# Steering_Controller.net
KiCad netlist of a schematic drawn in EAGLE
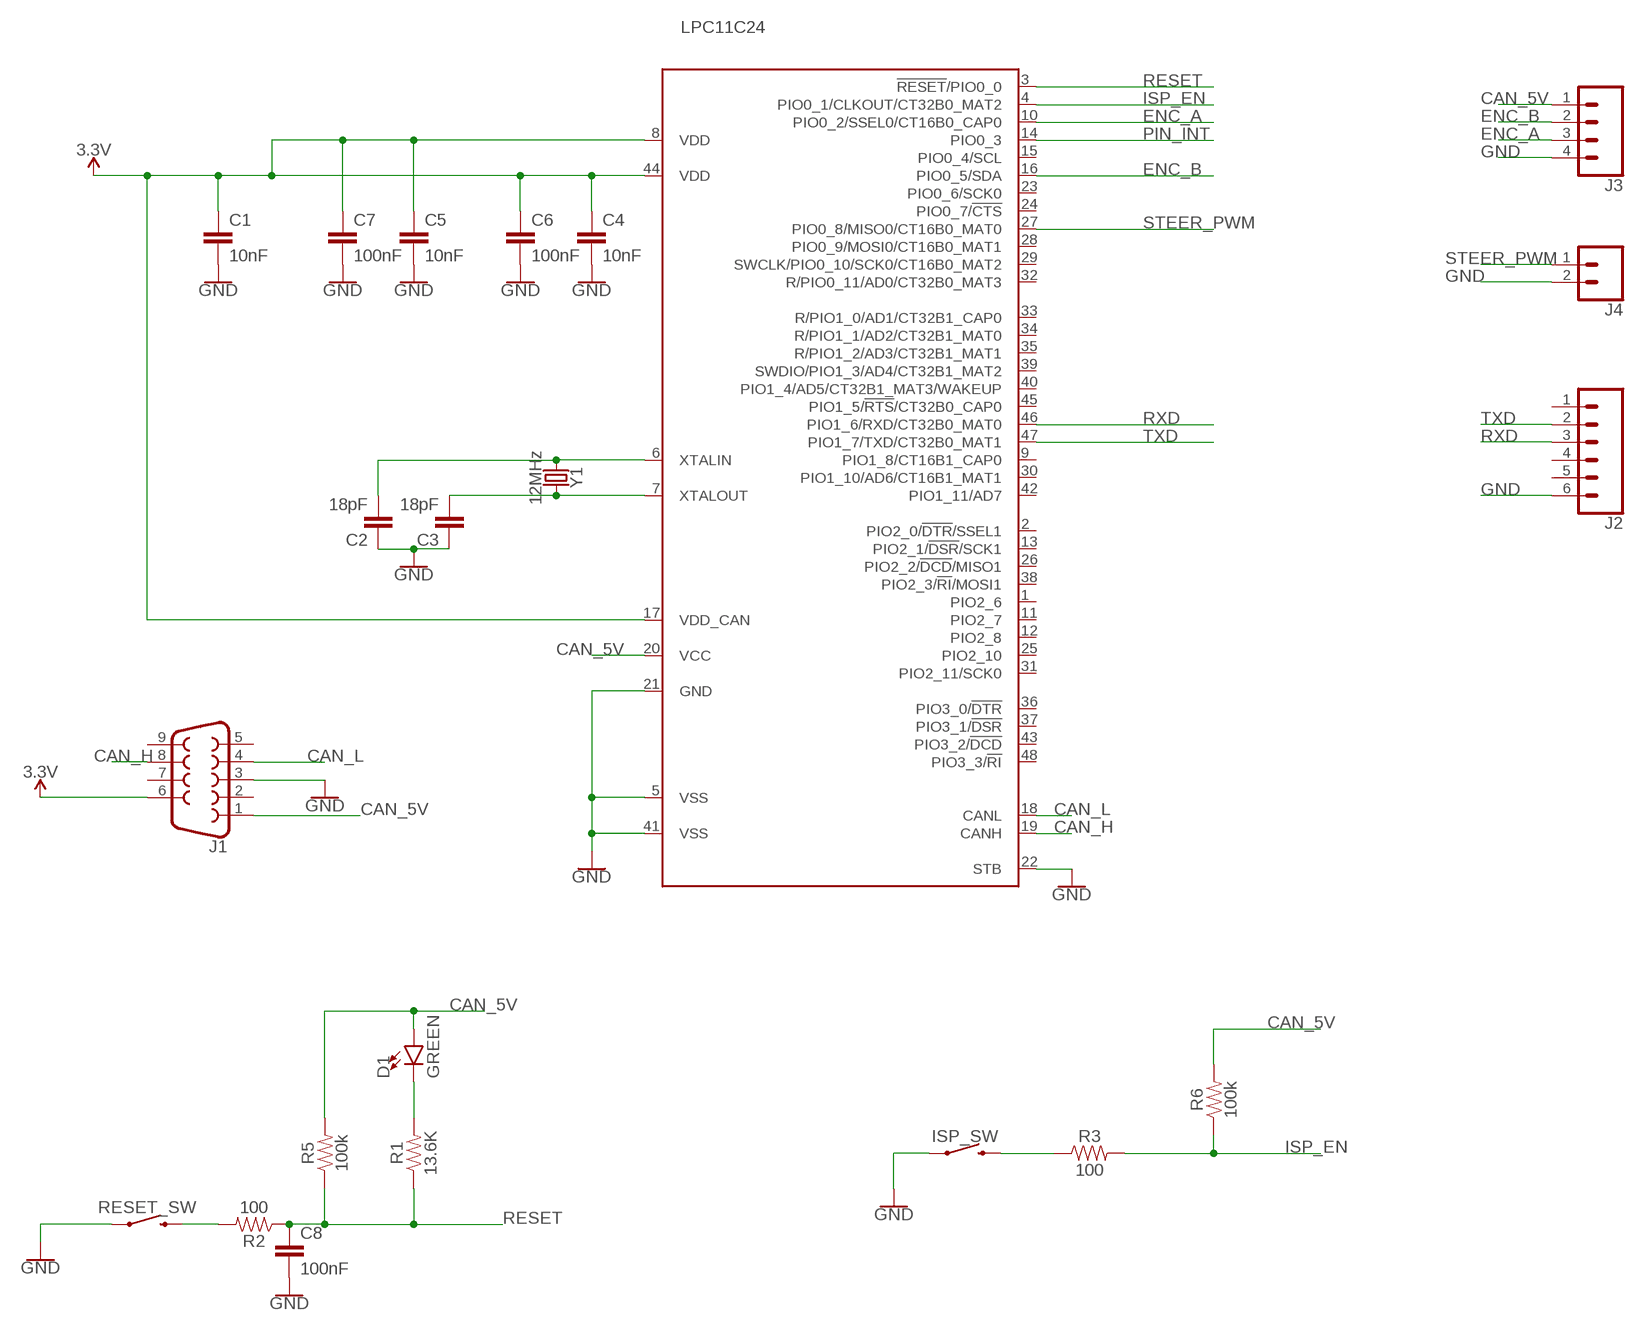
[diagram p0: schematic, sheet 1]

(export (version "E")
  (design (tool "Eeschema 10.0.6"))
  (components
    (comp (ref "C1")
      (value "10nF")
      (footprint "eagle-import:CAP-PTH-2.54")
      (libsource (lib "eagle-import") (part "22PF-PTH-2.54MM-200V-5%"))
    )
    (comp (ref "C2")
      (value "18pF")
      (footprint "eagle-import:CAP-PTH-2.54")
      (libsource (lib "eagle-import") (part "22PF-PTH-2.54MM-200V-5%"))
    )
    (comp (ref "C3")
      (value "18pF")
      (footprint "eagle-import:CAP-PTH-2.54")
      (libsource (lib "eagle-import") (part "22PF-PTH-2.54MM-200V-5%"))
    )
    (comp (ref "C4")
      (value "10nF")
      (footprint "eagle-import:CAP-PTH-2.54")
      (libsource (lib "eagle-import") (part "22PF-PTH-2.54MM-200V-5%"))
    )
    (comp (ref "C5")
      (value "10nF")
      (footprint "eagle-import:CAP-PTH-2.54")
      (libsource (lib "eagle-import") (part "22PF-PTH-2.54MM-200V-5%"))
    )
    (comp (ref "C6")
      (value "100nF")
      (footprint "eagle-import:CAP-PTH-2.54")
      (libsource (lib "eagle-import") (part "22PF-PTH-2.54MM-200V-5%"))
    )
    (comp (ref "C7")
      (value "100nF")
      (footprint "eagle-import:CAP-PTH-2.54")
      (libsource (lib "eagle-import") (part "22PF-PTH-2.54MM-200V-5%"))
    )
    (comp (ref "C8")
      (value "100nF")
      (footprint "eagle-import:CAP-PTH-2.54")
      (libsource (lib "eagle-import") (part "22PF-PTH-2.54MM-200V-5%"))
    )
    (comp (ref "D1")
      (value "GREEN")
      (footprint "eagle-import:LED-1206")
      (libsource (lib "eagle-import") (part "LED-GREEN1206"))
    )
    (comp (ref "ISP_SW")
      (value "MOMENTARY-SWITCH-SPST-PTH-6.0MM")
      (footprint "eagle-import:TACTILE_SWITCH_PTH_6.0MM")
      (libsource (lib "eagle-import") (part "MOMENTARY-SWITCH-SPST-PTH-6.0MM"))
    )
    (comp (ref "J1")
      (value "DB9FEMALE")
      (footprint "eagle-import:DB9")
      (libsource (lib "eagle-import") (part "DB9FEMALE"))
    )
    (comp (ref "J2")
      (value "CONN_06SILK_FEMALE_PTH")
      (footprint "eagle-import:1X06")
      (libsource (lib "eagle-import") (part "CONN_06SILK_FEMALE_PTH"))
    )
    (comp (ref "J3")
      (value "CONN_04")
      (footprint "eagle-import:1X04")
      (libsource (lib "eagle-import") (part "CONN_04"))
    )
    (comp (ref "J4")
      (value "CONN_02")
      (footprint "eagle-import:1X02")
      (libsource (lib "eagle-import") (part "CONN_02"))
    )
    (comp (ref "LPC11C24")
      (value "LPC11C22/24-LQFP48")
      (footprint "eagle-import:LQFP48")
      (libsource (lib "eagle-import") (part "LPC11C22/24-LQFP48"))
    )
    (comp (ref "R1")
      (value "13.6K")
      (footprint "eagle-import:AXIAL-0.3")
      (libsource (lib "eagle-import") (part "100KOHM-HORIZ-1/4W-1%"))
    )
    (comp (ref "R2")
      (value "100")
      (footprint "eagle-import:AXIAL-0.3")
      (libsource (lib "eagle-import") (part "100KOHM-HORIZ-1/4W-1%"))
    )
    (comp (ref "R3")
      (value "100")
      (footprint "eagle-import:AXIAL-0.3")
      (libsource (lib "eagle-import") (part "100OHM-HORIZ-1/4W-1%"))
    )
    (comp (ref "R5")
      (value "100k")
      (footprint "eagle-import:AXIAL-0.3")
      (libsource (lib "eagle-import") (part "100KOHM-HORIZ-1/4W-1%"))
    )
    (comp (ref "R6")
      (value "100k")
      (footprint "eagle-import:AXIAL-0.3")
      (libsource (lib "eagle-import") (part "100KOHM-HORIZ-1/4W-1%"))
    )
    (comp (ref "RESET_SW")
      (value "MOMENTARY-SWITCH-SPST-PTH-6.0MM")
      (footprint "eagle-import:TACTILE_SWITCH_PTH_6.0MM")
      (libsource (lib "eagle-import") (part "MOMENTARY-SWITCH-SPST-PTH-6.0MM"))
    )
    (comp (ref "Y1")
      (value "12MHz")
      (footprint "eagle-import:HC49US")
      (libsource (lib "eagle-import") (part "CRYSTAL-16MHZPTH-HC49US"))
    )
  )
  (nets
    (net (code "1") (name "/CAN_5V") (class "Default")
      (node (ref "D1") (pin "A") (pinfunction "A_A") (pintype "passive"))
      (node (ref "J1") (pin "1") (pinfunction "1_1") (pintype "passive"))
      (node (ref "J3") (pin "1") (pinfunction "1_1") (pintype "passive"))
      (node (ref "LPC11C24") (pin "20") (pinfunction "VCC_20") (pintype "power_in"))
      (node (ref "R5") (pin "P$2") (pinfunction "2_P$2") (pintype "passive"))
      (node (ref "R6") (pin "P$2") (pinfunction "2_P$2") (pintype "passive"))
    )
    (net (code "2") (name "/CAN_H") (class "Default")
      (node (ref "J1") (pin "8") (pinfunction "8_8") (pintype "passive"))
      (node (ref "LPC11C24") (pin "19") (pinfunction "CANH_19") (pintype "bidirectional"))
    )
    (net (code "3") (name "/CAN_L") (class "Default")
      (node (ref "J1") (pin "4") (pinfunction "4_4") (pintype "passive"))
      (node (ref "LPC11C24") (pin "18") (pinfunction "CANL_18") (pintype "bidirectional"))
    )
    (net (code "4") (name "/ENC_A") (class "Default")
      (node (ref "J3") (pin "3") (pinfunction "3_3") (pintype "passive"))
      (node (ref "LPC11C24") (pin "10") (pinfunction "PIO0_2/SSEL0/CT16B0_CAP0_10") (pintype "bidirectional"))
    )
    (net (code "5") (name "/ENC_B") (class "Default")
      (node (ref "J3") (pin "2") (pinfunction "2_2") (pintype "passive"))
      (node (ref "LPC11C24") (pin "16") (pinfunction "PIO0_5/SDA_16") (pintype "bidirectional"))
    )
    (net (code "6") (name "/ISP_EN") (class "Default")
      (node (ref "LPC11C24") (pin "4") (pinfunction "PIO0_1/CLKOUT/CT32B0_MAT2_4") (pintype "bidirectional"))
      (node (ref "R3") (pin "P$2") (pinfunction "2_P$2") (pintype "passive"))
      (node (ref "R6") (pin "P$1") (pinfunction "1_P$1") (pintype "passive"))
    )
    (net (code "7") (name "/PIN_INT") (class "Default")
      (node (ref "LPC11C24") (pin "14") (pinfunction "PIO0_3_14") (pintype "bidirectional"))
    )
    (net (code "8") (name "/RESET") (class "Default")
      (node (ref "C8") (pin "1") (pinfunction "1_1") (pintype "passive"))
      (node (ref "LPC11C24") (pin "3") (pinfunction "~{RESET}/PIO0_0_3") (pintype "bidirectional"))
      (node (ref "R1") (pin "P$1") (pinfunction "1_P$1") (pintype "passive"))
      (node (ref "R2") (pin "P$1") (pinfunction "1_P$1") (pintype "passive"))
      (node (ref "R5") (pin "P$1") (pinfunction "1_P$1") (pintype "passive"))
    )
    (net (code "9") (name "/RXD") (class "Default")
      (node (ref "J2") (pin "3") (pinfunction "3_3") (pintype "passive"))
      (node (ref "LPC11C24") (pin "46") (pinfunction "PIO1_6/RXD/CT32B0_MAT0_46") (pintype "bidirectional"))
    )
    (net (code "10") (name "/STEER_PWM") (class "Default")
      (node (ref "J4") (pin "1") (pinfunction "1_1") (pintype "passive"))
      (node (ref "LPC11C24") (pin "27") (pinfunction "PIO0_8/MISO0/CT16B0_MAT0_27") (pintype "bidirectional"))
    )
    (net (code "11") (name "/TXD") (class "Default")
      (node (ref "J2") (pin "2") (pinfunction "2_2") (pintype "passive"))
      (node (ref "LPC11C24") (pin "47") (pinfunction "PIO1_7/TXD/CT32B0_MAT1_47") (pintype "bidirectional"))
    )
    (net (code "12") (name "3.3V") (class "Default")
      (node (ref "C1") (pin "1") (pinfunction "1_1") (pintype "passive"))
      (node (ref "C4") (pin "1") (pinfunction "1_1") (pintype "passive"))
      (node (ref "C5") (pin "1") (pinfunction "1_1") (pintype "passive"))
      (node (ref "C6") (pin "1") (pinfunction "1_1") (pintype "passive"))
      (node (ref "C7") (pin "1") (pinfunction "1_1") (pintype "passive"))
      (node (ref "J1") (pin "6") (pinfunction "6_6") (pintype "passive"))
      (node (ref "LPC11C24") (pin "17") (pinfunction "VDD_CAN_17") (pintype "power_in"))
      (node (ref "LPC11C24") (pin "44") (pinfunction "VDD_44") (pintype "power_in"))
      (node (ref "LPC11C24") (pin "8") (pinfunction "VDD_8") (pintype "power_in"))
    )
    (net (code "13") (name "GND") (class "Default")
      (node (ref "C1") (pin "2") (pinfunction "2_2") (pintype "passive"))
      (node (ref "C2") (pin "1") (pinfunction "1_1") (pintype "passive"))
      (node (ref "C3") (pin "1") (pinfunction "1_1") (pintype "passive"))
      (node (ref "C4") (pin "2") (pinfunction "2_2") (pintype "passive"))
      (node (ref "C5") (pin "2") (pinfunction "2_2") (pintype "passive"))
      (node (ref "C6") (pin "2") (pinfunction "2_2") (pintype "passive"))
      (node (ref "C7") (pin "2") (pinfunction "2_2") (pintype "passive"))
      (node (ref "C8") (pin "2") (pinfunction "2_2") (pintype "passive"))
      (node (ref "ISP_SW") (pin "1") (pinfunction "1_1") (pintype "passive"))
      (node (ref "J1") (pin "3") (pinfunction "3_3") (pintype "passive"))
      (node (ref "J2") (pin "6") (pinfunction "6_6") (pintype "passive"))
      (node (ref "J3") (pin "4") (pinfunction "4_4") (pintype "passive"))
      (node (ref "J4") (pin "2") (pinfunction "2_2") (pintype "passive"))
      (node (ref "LPC11C24") (pin "21") (pinfunction "GND_21") (pintype "power_in"))
      (node (ref "LPC11C24") (pin "22") (pinfunction "STB_22") (pintype "bidirectional"))
      (node (ref "LPC11C24") (pin "41") (pinfunction "VSS_41") (pintype "power_in"))
      (node (ref "LPC11C24") (pin "5") (pinfunction "VSS_5") (pintype "power_in"))
      (node (ref "RESET_SW") (pin "1") (pinfunction "1_1") (pintype "passive"))
    )
    (net (code "14") (name "Net-(ISP_SW-2)") (class "Default")
      (node (ref "ISP_SW") (pin "3") (pinfunction "2_3") (pintype "passive"))
      (node (ref "R3") (pin "P$1") (pinfunction "1_P$1") (pintype "passive"))
    )
    (net (code "15") (name "Net-(LPC11C24-XTALIN)") (class "Default")
      (node (ref "C2") (pin "2") (pinfunction "2_2") (pintype "passive"))
      (node (ref "LPC11C24") (pin "6") (pinfunction "XTALIN_6") (pintype "passive"))
      (node (ref "Y1") (pin "1") (pinfunction "1_1") (pintype "passive"))
    )
    (net (code "16") (name "Net-(LPC11C24-XTALOUT)") (class "Default")
      (node (ref "C3") (pin "2") (pinfunction "2_2") (pintype "passive"))
      (node (ref "LPC11C24") (pin "7") (pinfunction "XTALOUT_7") (pintype "passive"))
      (node (ref "Y1") (pin "2") (pinfunction "2_2") (pintype "passive"))
    )
    (net (code "17") (name "Net-(R1-2)") (class "Default")
      (node (ref "D1") (pin "C") (pinfunction "C_C") (pintype "passive"))
      (node (ref "R1") (pin "P$2") (pinfunction "2_P$2") (pintype "passive"))
    )
    (net (code "18") (name "Net-(R2-2)") (class "Default")
      (node (ref "R2") (pin "P$2") (pinfunction "2_P$2") (pintype "passive"))
      (node (ref "RESET_SW") (pin "3") (pinfunction "2_3") (pintype "passive"))
    )
    (net (code "19") (name "unconnected-(J1-Pad2)") (class "Default")
      (node (ref "J1") (pin "2") (pinfunction "2_2") (pintype "passive"))
    )
    (net (code "20") (name "unconnected-(J1-Pad5)") (class "Default")
      (node (ref "J1") (pin "5") (pinfunction "5_5") (pintype "passive"))
    )
    (net (code "21") (name "unconnected-(J1-Pad7)") (class "Default")
      (node (ref "J1") (pin "7") (pinfunction "7_7") (pintype "passive"))
    )
    (net (code "22") (name "unconnected-(J1-Pad9)") (class "Default")
      (node (ref "J1") (pin "9") (pinfunction "9_9") (pintype "passive"))
    )
    (net (code "23") (name "unconnected-(J2-Pad1)") (class "Default")
      (node (ref "J2") (pin "1") (pinfunction "1_1") (pintype "passive"))
    )
    (net (code "24") (name "unconnected-(J2-Pad4)") (class "Default")
      (node (ref "J2") (pin "4") (pinfunction "4_4") (pintype "passive"))
    )
    (net (code "25") (name "unconnected-(J2-Pad5)") (class "Default")
      (node (ref "J2") (pin "5") (pinfunction "5_5") (pintype "passive"))
    )
    (net (code "26") (name "unconnected-(LPC11C24-PIO0_4{slash}SCL-Pad15)") (class "Default")
      (node (ref "LPC11C24") (pin "15") (pinfunction "PIO0_4/SCL_15") (pintype "bidirectional"))
    )
    (net (code "27") (name "unconnected-(LPC11C24-PIO0_6{slash}SCK0-Pad23)") (class "Default")
      (node (ref "LPC11C24") (pin "23") (pinfunction "PIO0_6/SCK0_23") (pintype "bidirectional"))
    )
    (net (code "28") (name "unconnected-(LPC11C24-PIO0_7{slash}~{CTS}-Pad24)") (class "Default")
      (node (ref "LPC11C24") (pin "24") (pinfunction "PIO0_7/~{CTS}_24") (pintype "bidirectional"))
    )
    (net (code "29") (name "unconnected-(LPC11C24-PIO0_9{slash}MOSI0{slash}CT16B0_MAT1-Pad28)") (class "Default")
      (node (ref "LPC11C24") (pin "28") (pinfunction "PIO0_9/MOSI0/CT16B0_MAT1_28") (pintype "bidirectional"))
    )
    (net (code "30") (name "unconnected-(LPC11C24-PIO1_4{slash}AD5{slash}CT32B1_MAT3{slash}WAKEUP-Pad40)") (class "Default")
      (node (ref "LPC11C24") (pin "40") (pinfunction "PIO1_4/AD5/CT32B1_MAT3/WAKEUP_40") (pintype "bidirectional"))
    )
    (net (code "31") (name "unconnected-(LPC11C24-PIO1_5{slash}~{RTS}{slash}CT32B0_CAP0-Pad45)") (class "Default")
      (node (ref "LPC11C24") (pin "45") (pinfunction "PIO1_5/~{RTS}/CT32B0_CAP0_45") (pintype "bidirectional"))
    )
    (net (code "32") (name "unconnected-(LPC11C24-PIO1_8{slash}CT16B1_CAP0-Pad9)") (class "Default")
      (node (ref "LPC11C24") (pin "9") (pinfunction "PIO1_8/CT16B1_CAP0_9") (pintype "bidirectional"))
    )
    (net (code "33") (name "unconnected-(LPC11C24-PIO1_10{slash}AD6{slash}CT16B1_MAT1-Pad30)") (class "Default")
      (node (ref "LPC11C24") (pin "30") (pinfunction "PIO1_10/AD6/CT16B1_MAT1_30") (pintype "bidirectional"))
    )
    (net (code "34") (name "unconnected-(LPC11C24-PIO1_11{slash}AD7-Pad42)") (class "Default")
      (node (ref "LPC11C24") (pin "42") (pinfunction "PIO1_11/AD7_42") (pintype "bidirectional"))
    )
    (net (code "35") (name "unconnected-(LPC11C24-PIO2_0{slash}~{DTR}{slash}SSEL1-Pad2)") (class "Default")
      (node (ref "LPC11C24") (pin "2") (pinfunction "PIO2_0/~{DTR}/SSEL1_2") (pintype "bidirectional"))
    )
    (net (code "36") (name "unconnected-(LPC11C24-PIO2_1{slash}~{DSR}{slash}SCK1-Pad13)") (class "Default")
      (node (ref "LPC11C24") (pin "13") (pinfunction "PIO2_1/~{DSR}/SCK1_13") (pintype "bidirectional"))
    )
    (net (code "37") (name "unconnected-(LPC11C24-PIO2_2{slash}~{DCD}{slash}MISO1-Pad26)") (class "Default")
      (node (ref "LPC11C24") (pin "26") (pinfunction "PIO2_2/~{DCD}/MISO1_26") (pintype "bidirectional"))
    )
    (net (code "38") (name "unconnected-(LPC11C24-PIO2_3{slash}~{RI}{slash}MOSI1-Pad38)") (class "Default")
      (node (ref "LPC11C24") (pin "38") (pinfunction "PIO2_3/~{RI}/MOSI1_38") (pintype "bidirectional"))
    )
    (net (code "39") (name "unconnected-(LPC11C24-PIO2_6-Pad1)") (class "Default")
      (node (ref "LPC11C24") (pin "1") (pinfunction "PIO2_6_1") (pintype "bidirectional"))
    )
    (net (code "40") (name "unconnected-(LPC11C24-PIO2_7-Pad11)") (class "Default")
      (node (ref "LPC11C24") (pin "11") (pinfunction "PIO2_7_11") (pintype "bidirectional"))
    )
    (net (code "41") (name "unconnected-(LPC11C24-PIO2_8-Pad12)") (class "Default")
      (node (ref "LPC11C24") (pin "12") (pinfunction "PIO2_8_12") (pintype "bidirectional"))
    )
    (net (code "42") (name "unconnected-(LPC11C24-PIO2_10-Pad25)") (class "Default")
      (node (ref "LPC11C24") (pin "25") (pinfunction "PIO2_10_25") (pintype "bidirectional"))
    )
    (net (code "43") (name "unconnected-(LPC11C24-PIO2_11{slash}SCK0-Pad31)") (class "Default")
      (node (ref "LPC11C24") (pin "31") (pinfunction "PIO2_11/SCK0_31") (pintype "bidirectional"))
    )
    (net (code "44") (name "unconnected-(LPC11C24-PIO3_0{slash}~{DTR}-Pad36)") (class "Default")
      (node (ref "LPC11C24") (pin "36") (pinfunction "PIO3_0/~{DTR}_36") (pintype "bidirectional"))
    )
    (net (code "45") (name "unconnected-(LPC11C24-PIO3_1{slash}~{DSR}-Pad37)") (class "Default")
      (node (ref "LPC11C24") (pin "37") (pinfunction "PIO3_1/~{DSR}_37") (pintype "bidirectional"))
    )
    (net (code "46") (name "unconnected-(LPC11C24-PIO3_2{slash}~{DCD}-Pad43)") (class "Default")
      (node (ref "LPC11C24") (pin "43") (pinfunction "PIO3_2/~{DCD}_43") (pintype "bidirectional"))
    )
    (net (code "47") (name "unconnected-(LPC11C24-PIO3_3{slash}~{RI}-Pad48)") (class "Default")
      (node (ref "LPC11C24") (pin "48") (pinfunction "PIO3_3/~{RI}_48") (pintype "bidirectional"))
    )
    (net (code "48") (name "unconnected-(LPC11C24-R{slash}PIO0_11{slash}AD0{slash}CT32B0_MAT3-Pad32)") (class "Default")
      (node (ref "LPC11C24") (pin "32") (pinfunction "R/PIO0_11/AD0/CT32B0_MAT3_32") (pintype "bidirectional"))
    )
    (net (code "49") (name "unconnected-(LPC11C24-R{slash}PIO1_0{slash}AD1{slash}CT32B1_CAP0-Pad33)") (class "Default")
      (node (ref "LPC11C24") (pin "33") (pinfunction "R/PIO1_0/AD1/CT32B1_CAP0_33") (pintype "bidirectional"))
    )
    (net (code "50") (name "unconnected-(LPC11C24-R{slash}PIO1_1{slash}AD2{slash}CT32B1_MAT0-Pad34)") (class "Default")
      (node (ref "LPC11C24") (pin "34") (pinfunction "R/PIO1_1/AD2/CT32B1_MAT0_34") (pintype "bidirectional"))
    )
    (net (code "51") (name "unconnected-(LPC11C24-R{slash}PIO1_2{slash}AD3{slash}CT32B1_MAT1-Pad35)") (class "Default")
      (node (ref "LPC11C24") (pin "35") (pinfunction "R/PIO1_2/AD3/CT32B1_MAT1_35") (pintype "bidirectional"))
    )
    (net (code "52") (name "unconnected-(LPC11C24-SWCLK{slash}PIO0_10{slash}SCK0{slash}CT16B0_MAT2-Pad29)") (class "Default")
      (node (ref "LPC11C24") (pin "29") (pinfunction "SWCLK/PIO0_10/SCK0/CT16B0_MAT2_29") (pintype "bidirectional"))
    )
    (net (code "53") (name "unconnected-(LPC11C24-SWDIO{slash}PIO1_3{slash}AD4{slash}CT32B1_MAT2-Pad39)") (class "Default")
      (node (ref "LPC11C24") (pin "39") (pinfunction "SWDIO/PIO1_3/AD4/CT32B1_MAT2_39") (pintype "bidirectional"))
    )
  )
)
